# button_peripheral.net
KiCad netlist of a schematic drawn in Altium Designer
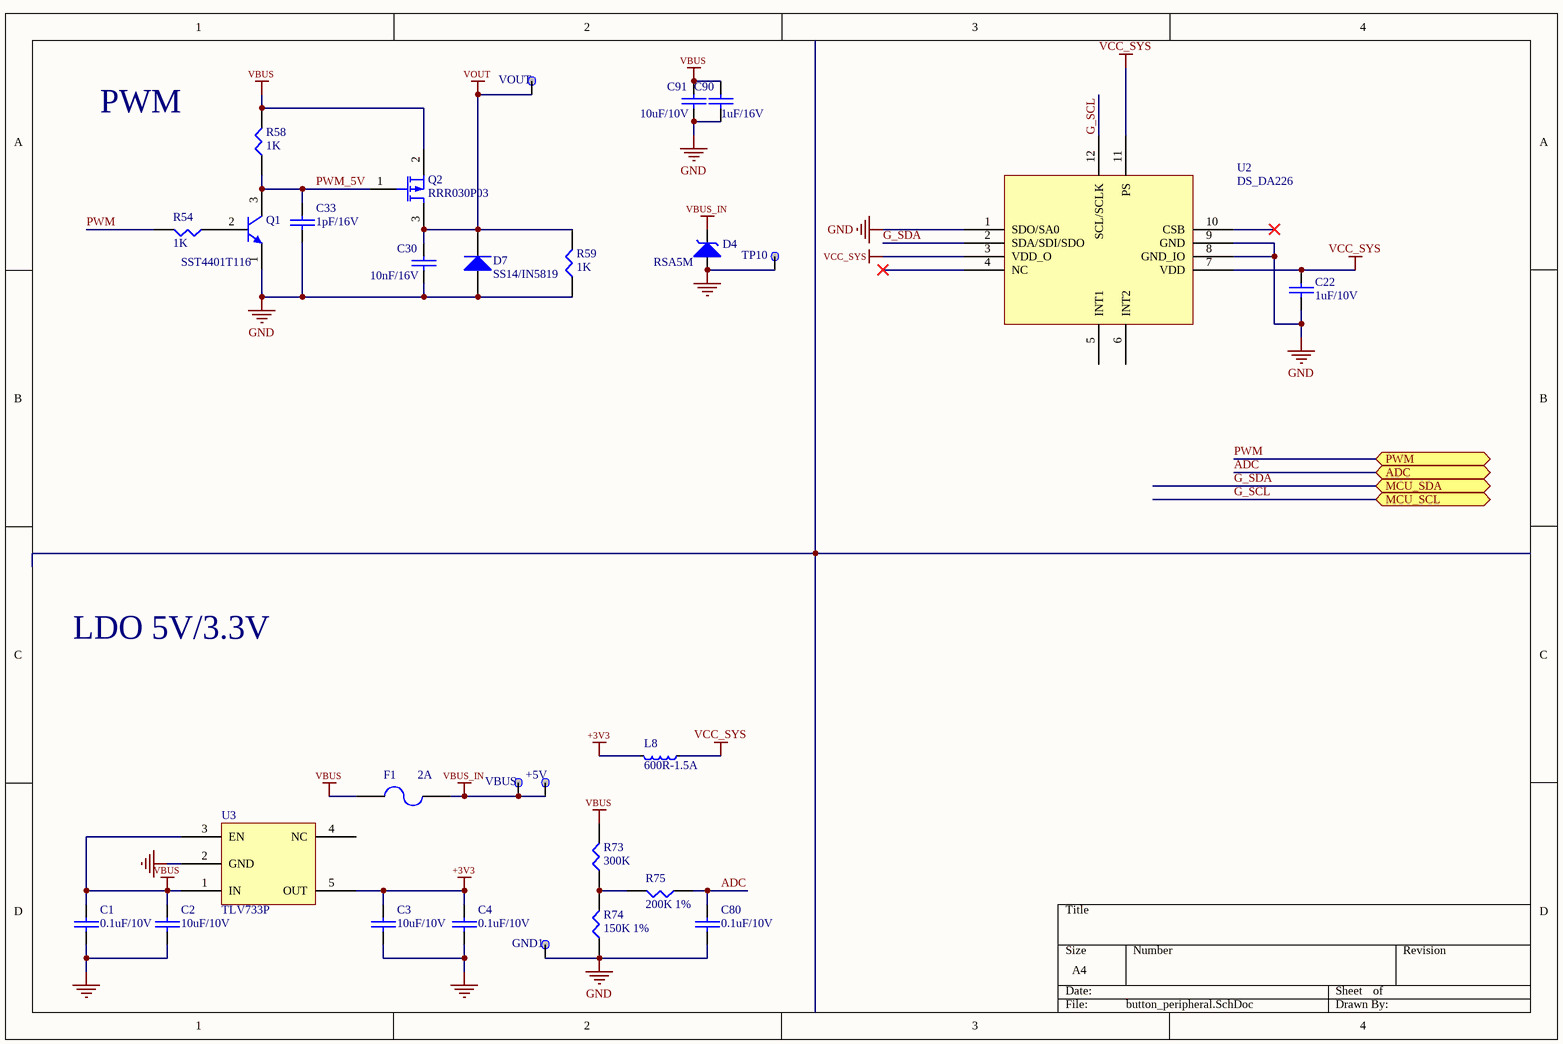
[diagram p0: button_peripheral.SchDoc]

(export (version "E")
  (design (tool "Eeschema 10.0.6"))
  (components
    (comp (ref "+5V") (value "TP") (footprint "TESTPOINT2") (libsource (lib "Almos") (part "TP")))
    (comp (ref "C1")
      (value "0.1uF/10V")
      (footprint "0402C")
      (description "厂家：Murata，型号：GRM155R71A104KA01D")
      (libsource (lib "*") (part "CAP"))
    )
    (comp (ref "C2")
      (value "10uF/10V")
      (footprint "0603C")
      (description "厂家：Murata，型号：GRM188R61A106KE69D")
      (libsource (lib "*") (part "CAP"))
    )
    (comp (ref "C3")
      (value "10uF/10V")
      (footprint "0603C")
      (description "厂家：Murata，型号：GRM188R61A106KE69D")
      (libsource (lib "*") (part "CAP"))
    )
    (comp (ref "C4")
      (value "0.1uF/10V")
      (footprint "0402C")
      (description "厂家：Murata，型号：GRM155R71A104KA01D")
      (libsource (lib "*") (part "CAP"))
    )
    (comp (ref "C22")
      (value "1uF/10V")
      (footprint "0402C")
      (description "厂家：Murata，型号：GRM155R71A104KA01D")
      (libsource (lib "*") (part "CAP"))
    )
    (comp (ref "C30")
      (value "10nF/16V")
      (footprint "0402C")
      (description "厂家：Murata，型号：GRM155R71A104KA01D")
      (libsource (lib "*") (part "CAP"))
    )
    (comp (ref "C33")
      (value "1pF/16V")
      (footprint "0402C")
      (description "厂家：Murata，型号：GRM155R71A104KA01D")
      (libsource (lib "*") (part "CAP"))
    )
    (comp (ref "C80")
      (value "0.1uF/10V")
      (footprint "0402C")
      (description "厂家：Murata，型号：GRM155R71A104KA01D")
      (libsource (lib "*") (part "CAP"))
    )
    (comp (ref "C90")
      (value "1uF/16V")
      (footprint "0603C")
      (description "厂家：Murata，型号：GRM188R61A106KE69D")
      (libsource (lib "*") (part "CAP"))
    )
    (comp (ref "C91")
      (value "10uF/10V")
      (footprint "LC-CASE-P_2012")
      (description "厂家：Murata，型号：GRM188R61A106KE69D")
      (libsource (lib "*") (part "CAP"))
    )
    (comp (ref "D4")
      (value "RSA5M")
      (footprint "SOD-123")
      (description "厂家：ROHM，型号：VMNZC6.8CST2RA")
      (libsource (lib "CCS801 VOC") (part "ESD_1"))
    )
    (comp (ref "D7")
      (value "SS14/IN5819")
      (footprint "PROGRAM_1/2")
      (description "High Conductance Fast Diode")
      (libsource (lib "Tools") (part "Diode 1N4148"))
    )
    (comp (ref "F1")
      (value "2A")
      (footprint "0805")
      (description "厂家：万瑞和，型号：smd1206-200")
      (libsource (lib "*") (part "FUSE2"))
    )
    (comp (ref "GND1") (value "TP") (footprint "TESTPOINT_PAD") (libsource (lib "Almos") (part "TP")))
    (comp (ref "L8")
      (value "600R-1.5A")
      (footprint "L_0603")
      (description "High frequency chip inductor ±5%")
      (fields
        (field (name "PART NUMBER") "L0402-27n")
        (field (name "MANUFACTURER") "Murata")
        (field (name "PUBLISHER") "Nordic Semiconductor")
      )
      (libsource (lib "Nordic Passive DB") (part "IND"))
    )
    (comp (ref "Q1")
      (value "SST4401T116")
      (footprint "LC-SOT-23(SOT-23-3)")
      (description "NPN General Purpose Amplifier")
      (fields (field (name "PUBLISHER") "Altium Limited"))
      (libsource (lib "常用sch库") (part "2N3904"))
    )
    (comp (ref "Q2")
      (value "RRR030P03")
      (footprint "TSMT3")
      (description "P-Channel MOSFET")
      (fields (field (name "PUBLISHER") "Altium Limited"))
      (libsource (lib "常用sch库") (part "MOSFET-P"))
    )
    (comp (ref "R54")
      (value "1K")
      (footprint "0402R")
      (description "厂家：Yageo，型号：RC0402FR-0720RL")
      (libsource (lib "*") (part "RES1"))
    )
    (comp (ref "R58")
      (value "1K")
      (footprint "0402R")
      (description "厂家：Yageo，型号：RC0402FR-0720RL")
      (libsource (lib "*") (part "RES1"))
    )
    (comp (ref "R59")
      (value "1K")
      (footprint "0402R")
      (description "厂家：Yageo，型号：RC0402FR-0720RL")
      (libsource (lib "*") (part "RES1"))
    )
    (comp (ref "R73")
      (value "300K")
      (footprint "0402R")
      (description "厂家：Yageo，型号：RC0402FR-0720RL")
      (libsource (lib "*") (part "RES1"))
    )
    (comp (ref "R74")
      (value "150K 1%")
      (footprint "0402R")
      (description "厂家：Yageo，型号：RC0402FR-0720RL")
      (libsource (lib "*") (part "RES1"))
    )
    (comp (ref "R75")
      (value "200K 1%")
      (footprint "0402R")
      (description "厂家：Yageo，型号：RC0402FR-0720RL")
      (libsource (lib "*") (part "RES1"))
    )
    (comp (ref "TP10") (value "TP") (footprint "TESTPOINT_PAD") (libsource (lib "Almos") (part "TP")))
    (comp (ref "U2")
      (value "DS_DA226")
      (footprint "LGA-12")
      (description "厂家：ST，型号：LIS2DH12")
      (libsource (lib "Debug Pinborad") (part "LIS2DE12"))
    )
    (comp (ref "U3") (value "TLV733P") (footprint "SOT-23-5") (libsource (lib "Tools") (part "AP3410")))
    (comp (ref "VBUS") (value "TP") (footprint "TESTPOINT_PAD") (libsource (lib "Almos") (part "TP")))
    (comp (ref "VOUT") (value "TP") (footprint "TESTPOINT_PAD") (libsource (lib "Almos") (part "TP")))
  )
  (nets
    (net (code "1") (name "+3V3") (class "Default")
      (node (ref "C3") (pin "1") (pinfunction "1_1") (pintype "passive"))
      (node (ref "C4") (pin "1") (pinfunction "1_1") (pintype "passive"))
      (node (ref "L8") (pin "2") (pinfunction "2_2") (pintype "passive"))
      (node (ref "U3") (pin "5") (pinfunction "OUT_5") (pintype "passive"))
    )
    (net (code "2") (name "/ADC") (class "Default")
      (node (ref "C80") (pin "1") (pinfunction "1_1") (pintype "passive"))
      (node (ref "R75") (pin "1") (pinfunction "1_1") (pintype "passive"))
    )
    (net (code "3") (name "/G_SCL") (class "Default")
      (node (ref "U2") (pin "12") (pinfunction "SCL/SCLK_12") (pintype "passive"))
    )
    (net (code "4") (name "/G_SDA") (class "Default")
      (node (ref "U2") (pin "2") (pinfunction "SDA/SDI/SDO_2") (pintype "passive"))
    )
    (net (code "5") (name "/PWM") (class "Default")
      (node (ref "R54") (pin "2") (pinfunction "2_2") (pintype "passive"))
    )
    (net (code "6") (name "/PWM_5V") (class "Default")
      (node (ref "C33") (pin "1") (pinfunction "1_1") (pintype "passive"))
      (node (ref "Q1") (pin "3") (pinfunction "C_3") (pintype "passive"))
      (node (ref "Q2") (pin "1") (pinfunction "G_1") (pintype "passive"))
      (node (ref "R58") (pin "1") (pinfunction "1_1") (pintype "passive"))
    )
    (net (code "7") (name "GND") (class "Default")
      (node (ref "C1") (pin "2") (pinfunction "2_2") (pintype "passive"))
      (node (ref "C2") (pin "2") (pinfunction "2_2") (pintype "passive"))
      (node (ref "C22") (pin "2") (pinfunction "2_2") (pintype "passive"))
      (node (ref "C3") (pin "2") (pinfunction "2_2") (pintype "passive"))
      (node (ref "C30") (pin "2") (pinfunction "2_2") (pintype "passive"))
      (node (ref "C33") (pin "2") (pinfunction "2_2") (pintype "passive"))
      (node (ref "C4") (pin "2") (pinfunction "2_2") (pintype "passive"))
      (node (ref "C80") (pin "2") (pinfunction "2_2") (pintype "passive"))
      (node (ref "C90") (pin "2") (pinfunction "2_2") (pintype "passive"))
      (node (ref "C91") (pin "2") (pinfunction "2_2") (pintype "passive"))
      (node (ref "D4") (pin "2") (pinfunction "dIode2_2") (pintype "passive"))
      (node (ref "D7") (pin "2") (pinfunction "A_2") (pintype "passive"))
      (node (ref "GND1") (pin "1") (pinfunction "1_1") (pintype "passive"))
      (node (ref "Q1") (pin "1") (pinfunction "E_1") (pintype "passive"))
      (node (ref "R59") (pin "1") (pinfunction "1_1") (pintype "passive"))
      (node (ref "R74") (pin "1") (pinfunction "1_1") (pintype "passive"))
      (node (ref "TP10") (pin "1") (pinfunction "1_1") (pintype "passive"))
      (node (ref "U2") (pin "1") (pinfunction "SDO/SA0_1") (pintype "passive"))
      (node (ref "U2") (pin "8") (pinfunction "GND_IO_8") (pintype "passive"))
      (node (ref "U2") (pin "9") (pinfunction "GND_9") (pintype "passive"))
      (node (ref "U3") (pin "2") (pinfunction "GND_2") (pintype "passive"))
    )
    (net (code "8") (name "Net-(Q1-B)") (class "Default")
      (node (ref "Q1") (pin "2") (pinfunction "B_2") (pintype "passive"))
      (node (ref "R54") (pin "1") (pinfunction "1_1") (pintype "passive"))
    )
    (net (code "9") (name "Net-(R73-Pad1)") (class "Default")
      (node (ref "R73") (pin "1") (pinfunction "1_1") (pintype "passive"))
      (node (ref "R74") (pin "2") (pinfunction "2_2") (pintype "passive"))
      (node (ref "R75") (pin "2") (pinfunction "2_2") (pintype "passive"))
    )
    (net (code "10") (name "VBUS") (class "Default")
      (node (ref "C1") (pin "1") (pinfunction "1_1") (pintype "passive"))
      (node (ref "C2") (pin "1") (pinfunction "1_1") (pintype "passive"))
      (node (ref "C90") (pin "1") (pinfunction "1_1") (pintype "passive"))
      (node (ref "C91") (pin "1") (pinfunction "1_1") (pintype "passive"))
      (node (ref "F1") (pin "1") (pinfunction "1_1") (pintype "passive"))
      (node (ref "Q2") (pin "2") (pinfunction "S_2") (pintype "passive"))
      (node (ref "R58") (pin "2") (pinfunction "2_2") (pintype "passive"))
      (node (ref "R73") (pin "2") (pinfunction "2_2") (pintype "passive"))
      (node (ref "U3") (pin "1") (pinfunction "IN_1") (pintype "passive"))
      (node (ref "U3") (pin "3") (pinfunction "EN_3") (pintype "passive"))
    )
    (net (code "11") (name "VBUS_IN") (class "Default")
      (node (ref "+5V") (pin "1") (pinfunction "1_1") (pintype "passive"))
      (node (ref "D4") (pin "1") (pinfunction "Diode1_1") (pintype "passive"))
      (node (ref "F1") (pin "2") (pinfunction "2_2") (pintype "passive"))
      (node (ref "VBUS") (pin "1") (pinfunction "1_1") (pintype "passive"))
    )
    (net (code "12") (name "VCC_SYS") (class "Default")
      (node (ref "C22") (pin "1") (pinfunction "1_1") (pintype "passive"))
      (node (ref "L8") (pin "1") (pinfunction "1_1") (pintype "passive"))
      (node (ref "U2") (pin "11") (pinfunction "PS_11") (pintype "passive"))
      (node (ref "U2") (pin "3") (pinfunction "VDD_O_3") (pintype "passive"))
      (node (ref "U2") (pin "7") (pinfunction "VDD_7") (pintype "passive"))
    )
    (net (code "13") (name "VOUT") (class "Default")
      (node (ref "C30") (pin "1") (pinfunction "1_1") (pintype "passive"))
      (node (ref "D7") (pin "1") (pinfunction "K_1") (pintype "passive"))
      (node (ref "Q2") (pin "3") (pinfunction "D_3") (pintype "passive"))
      (node (ref "R59") (pin "2") (pinfunction "2_2") (pintype "passive"))
      (node (ref "VOUT") (pin "1") (pinfunction "1_1") (pintype "passive"))
    )
    (net (code "14") (name "unconnected-(U2-CSB-Pad10)") (class "Default")
      (node (ref "U2") (pin "10") (pinfunction "CSB_10") (pintype "passive+no_connect"))
    )
    (net (code "15") (name "unconnected-(U2-INT1-Pad5)") (class "Default")
      (node (ref "U2") (pin "5") (pinfunction "INT1_5") (pintype "passive"))
    )
    (net (code "16") (name "unconnected-(U2-INT2-Pad6)") (class "Default")
      (node (ref "U2") (pin "6") (pinfunction "INT2_6") (pintype "passive"))
    )
    (net (code "17") (name "unconnected-(U2-NC-Pad4)") (class "Default")
      (node (ref "U2") (pin "4") (pinfunction "NC_4") (pintype "passive+no_connect"))
    )
    (net (code "18") (name "unconnected-(U3-NC-Pad4)") (class "Default")
      (node (ref "U3") (pin "4") (pinfunction "NC_4") (pintype "passive"))
    )
  )
)
